# mb_01-4.net
KiCad netlist of a schematic drawn in EAGLE
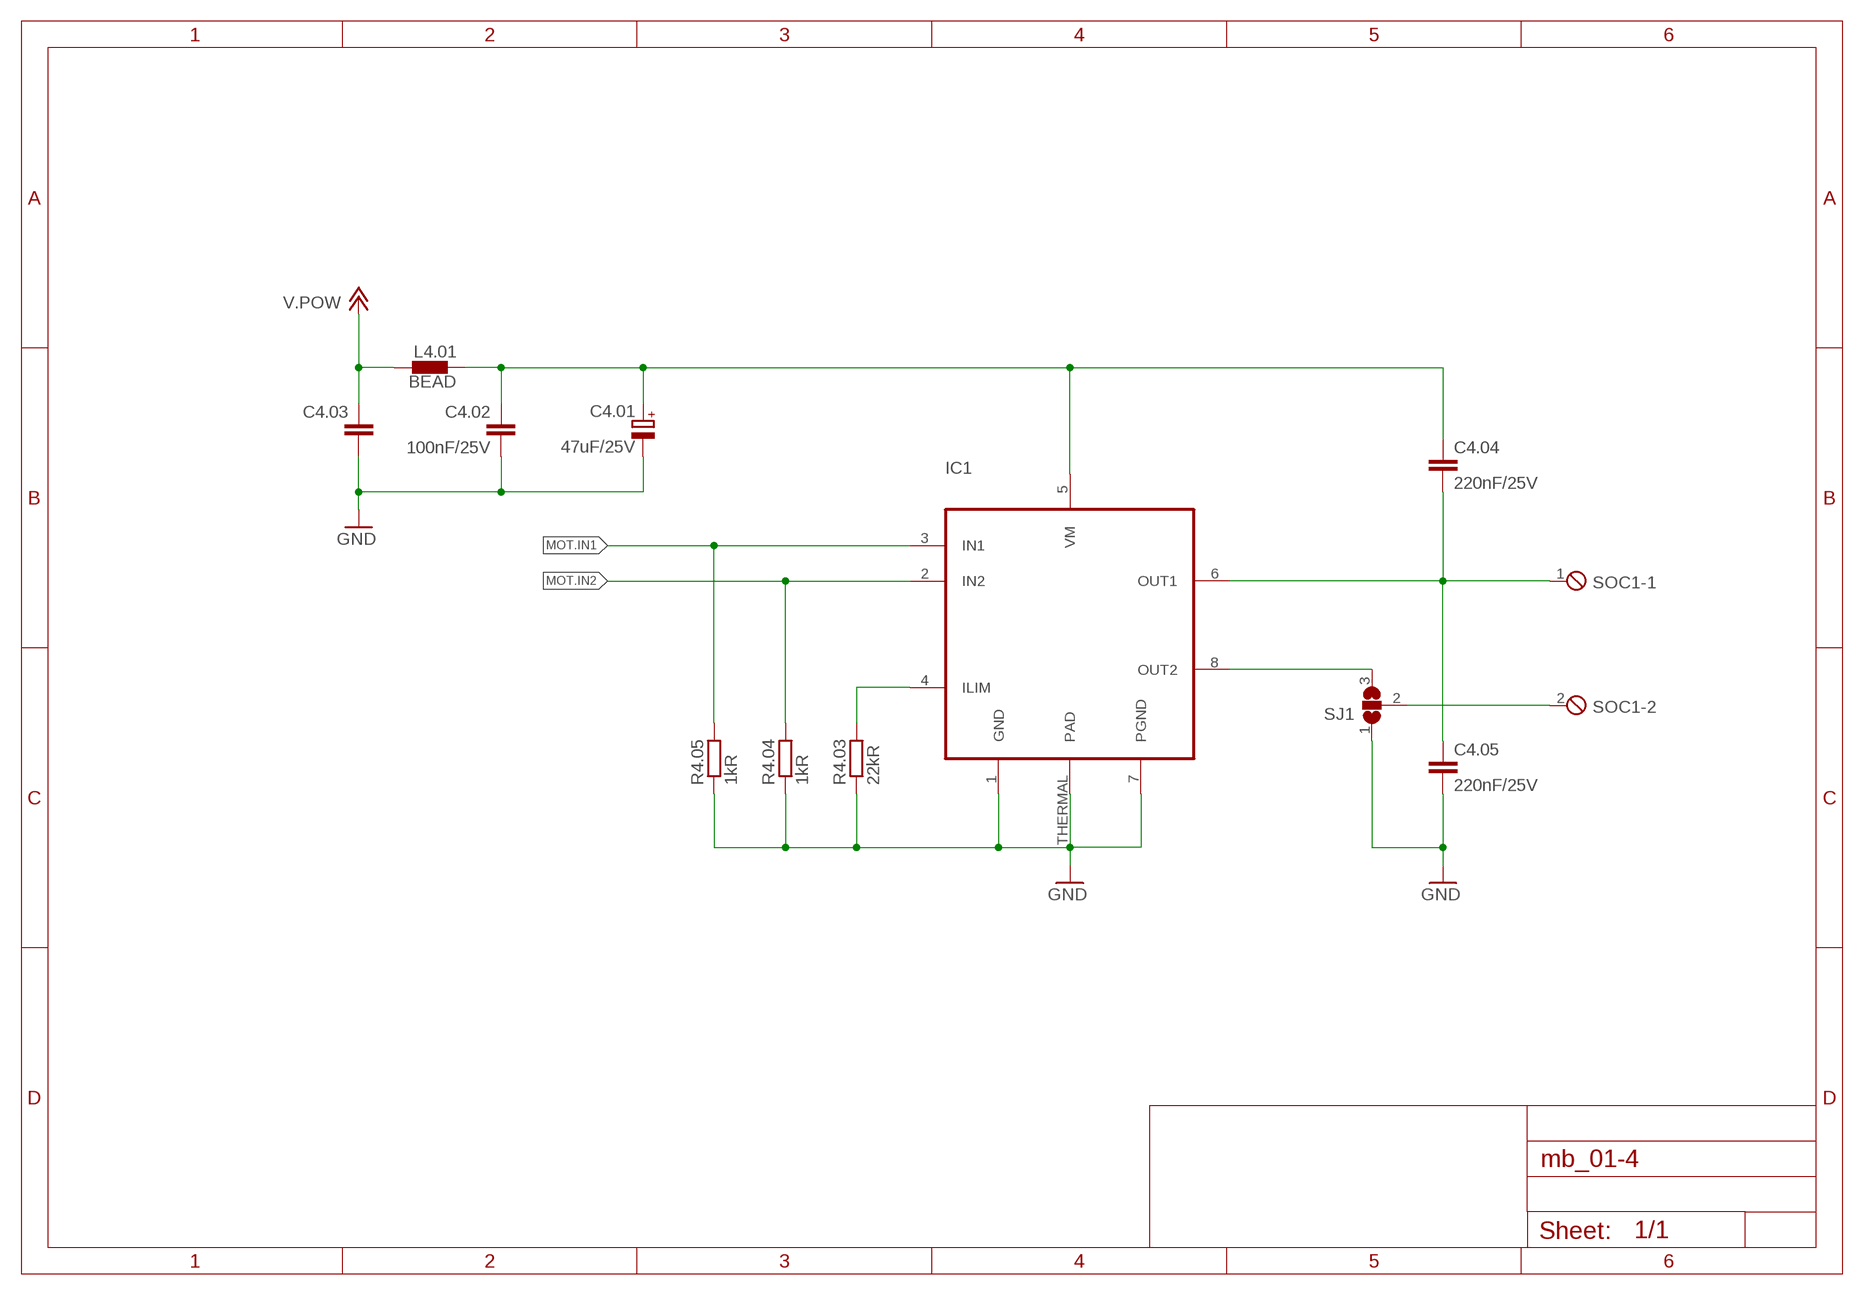
[diagram p0: schematic, sheet 1]

(export (version "E")
  (design (tool "Eeschema 10.0.6"))
  (components
    (comp (ref "C4.01")
      (value "47uF/25V")
      (footprint "eagle-import:C_6032-28R")
      (libsource (lib "eagle-import") (part "CPOL-EUC/6032-28R"))
    )
    (comp (ref "C4.02")
      (value "100nF/25V")
      (footprint "eagle-import:C0603K")
      (libsource (lib "eagle-import") (part "resistor_C-EUC0603K"))
    )
    (comp (ref "C4.03")
      (value "C-EUC0805K")
      (footprint "eagle-import:C0805K")
      (libsource (lib "eagle-import") (part "resistor_C-EUC0805K"))
    )
    (comp (ref "C4.04")
      (value "220nF/25V")
      (footprint "eagle-import:C0603K")
      (libsource (lib "eagle-import") (part "C-EUC0603K"))
    )
    (comp (ref "C4.05")
      (value "220nF/25V")
      (footprint "eagle-import:C0603K")
      (libsource (lib "eagle-import") (part "C-EUC0603K"))
    )
    (comp (ref "IC1")
      (value "DRV8871")
      (footprint "eagle-import:HSOP8")
      (libsource (lib "eagle-import") (part "DRV8871"))
    )
    (comp (ref "L4.01")
      (value "BEAD")
      (footprint "eagle-import:0402")
      (libsource (lib "eagle-import") (part "BLM15HB121SN1"))
    )
    (comp (ref "R4.03")
      (value "22kR")
      (footprint "eagle-import:R0402")
      (libsource (lib "eagle-import") (part "R-EU_R0402"))
    )
    (comp (ref "R4.04")
      (value "1kR")
      (footprint "eagle-import:R0402")
      (libsource (lib "eagle-import") (part "R-EU_R0402"))
    )
    (comp (ref "R4.05")
      (value "1kR")
      (footprint "eagle-import:R0402")
      (libsource (lib "eagle-import") (part "R-EU_R0402"))
    )
    (comp (ref "SJ1")
      (value "SJ2W")
      (footprint "eagle-import:SJ_2")
      (libsource (lib "eagle-import") (part "SJ2W"))
    )
    (comp (ref "SOC1")
      (value "MPT2")
      (footprint "eagle-import:2POL254")
      (libsource (lib "eagle-import") (part "MPT2"))
    )
  )
  (nets
    (net (code "1") (name "GND") (class "Default")
      (node (ref "C4.01") (pin "-") (pinfunction "-_-") (pintype "passive"))
      (node (ref "C4.02") (pin "2") (pinfunction "2_2") (pintype "passive"))
      (node (ref "C4.03") (pin "2") (pinfunction "2_2") (pintype "passive"))
      (node (ref "C4.05") (pin "2") (pinfunction "2_2") (pintype "passive"))
      (node (ref "IC1") (pin "1") (pinfunction "GND_1") (pintype "bidirectional"))
      (node (ref "IC1") (pin "7") (pinfunction "PGND_7") (pintype "bidirectional"))
      (node (ref "IC1") (pin "THERMAL") (pinfunction "PAD_THERMAL") (pintype "bidirectional"))
      (node (ref "R4.03") (pin "1") (pinfunction "1_1") (pintype "passive"))
      (node (ref "R4.04") (pin "1") (pinfunction "1_1") (pintype "passive"))
      (node (ref "R4.05") (pin "1") (pinfunction "1_1") (pintype "passive"))
      (node (ref "SJ1") (pin "1") (pinfunction "1_1") (pintype "passive"))
    )
    (net (code "2") (name "MOT.IN1") (class "Default")
      (node (ref "IC1") (pin "3") (pinfunction "IN1_3") (pintype "bidirectional"))
      (node (ref "R4.05") (pin "2") (pinfunction "2_2") (pintype "passive"))
    )
    (net (code "3") (name "MOT.IN2") (class "Default")
      (node (ref "IC1") (pin "2") (pinfunction "IN2_2") (pintype "bidirectional"))
      (node (ref "R4.04") (pin "2") (pinfunction "2_2") (pintype "passive"))
    )
    (net (code "4") (name "Net-(IC1-ILIM)") (class "Default")
      (node (ref "IC1") (pin "4") (pinfunction "ILIM_4") (pintype "bidirectional"))
      (node (ref "R4.03") (pin "2") (pinfunction "2_2") (pintype "passive"))
    )
    (net (code "5") (name "Net-(IC1-OUT1)") (class "Default")
      (node (ref "C4.04") (pin "2") (pinfunction "2_2") (pintype "passive"))
      (node (ref "C4.05") (pin "1") (pinfunction "1_1") (pintype "passive"))
      (node (ref "IC1") (pin "6") (pinfunction "OUT1_6") (pintype "bidirectional"))
      (node (ref "SOC1") (pin "1") (pinfunction "1_1") (pintype "passive"))
    )
    (net (code "6") (name "Net-(IC1-OUT2)") (class "Default")
      (node (ref "IC1") (pin "8") (pinfunction "OUT2_8") (pintype "bidirectional"))
      (node (ref "SJ1") (pin "3") (pinfunction "3_3") (pintype "passive"))
    )
    (net (code "7") (name "Net-(IC1-VM)") (class "Default")
      (node (ref "C4.01") (pin "+") (pinfunction "+_+") (pintype "passive"))
      (node (ref "C4.02") (pin "1") (pinfunction "1_1") (pintype "passive"))
      (node (ref "C4.04") (pin "1") (pinfunction "1_1") (pintype "passive"))
      (node (ref "IC1") (pin "5") (pinfunction "VM_5") (pintype "bidirectional"))
      (node (ref "L4.01") (pin "1") (pinfunction "1_1") (pintype "passive"))
    )
    (net (code "8") (name "Net-(SOC1B-1)") (class "Default")
      (node (ref "SJ1") (pin "2") (pinfunction "2_2") (pintype "passive"))
      (node (ref "SOC1") (pin "2") (pinfunction "1_2") (pintype "passive"))
    )
    (net (code "9") (name "V.POW") (class "Default")
      (node (ref "C4.03") (pin "1") (pinfunction "1_1") (pintype "passive"))
      (node (ref "L4.01") (pin "2") (pinfunction "2_2") (pintype "passive"))
    )
  )
)
